# Accelerometer.net
KiCad netlist of a schematic drawn in Altium Designer
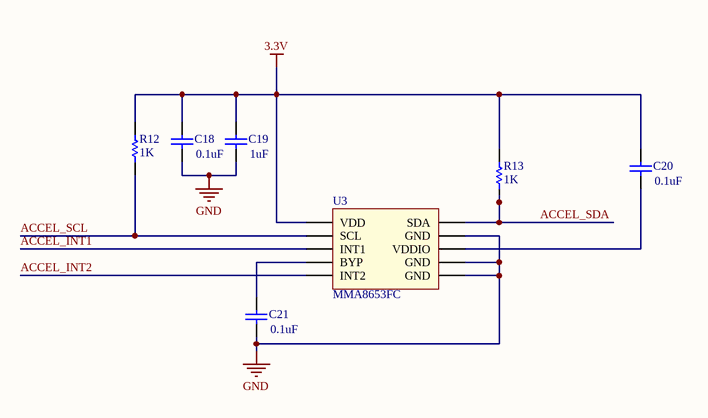
[diagram p0: Accelerometer.SchDoc]

(export (version "E")
  (design (tool "Eeschema 10.0.6"))
  (components
    (comp (ref "C18")
      (value "0.1uF")
      (footprint "0805")
      (description "Capacitor")
      (fields (field (name "Comment") "Cap"))
      (libsource (lib "passives") (part "Cap"))
    )
    (comp (ref "C19")
      (value "1uF")
      (footprint "0805")
      (description "Capacitor")
      (fields (field (name "Comment") "Cap"))
      (libsource (lib "passives") (part "Cap"))
    )
    (comp (ref "C20")
      (value "0.1uF")
      (footprint "0805")
      (description "Capacitor")
      (fields (field (name "Comment") "Cap"))
      (libsource (lib "passives") (part "Cap"))
    )
    (comp (ref "C21")
      (value "0.1uF")
      (footprint "0805")
      (description "Capacitor")
      (fields (field (name "Comment") "Cap"))
      (libsource (lib "passives") (part "Cap"))
    )
    (comp (ref "R12")
      (value "1K")
      (footprint "0805")
      (description "Resistor")
      (fields (field (name "PUBLISHER") "Altium Limited"))
      (libsource (lib "passives") (part "Resistor"))
    )
    (comp (ref "R13")
      (value "1K")
      (footprint "0805")
      (description "Resistor")
      (fields (field (name "PUBLISHER") "Altium Limited"))
      (libsource (lib "passives") (part "Resistor"))
    )
    (comp (ref "U3")
      (value "MMA8653FC")
      (footprint "DFN-10")
      (description "MMA8653FC Accelerometer 3-Axis")
      (libsource (lib "Devices") (part "MMA8653FC"))
    )
  )
  (nets
    (net (code "1") (name "/ACCEL_INT1") (class "Default")
      (node (ref "U3") (pin "3") (pinfunction "INT1_3") (pintype "passive"))
    )
    (net (code "2") (name "/ACCEL_INT2") (class "Default")
      (node (ref "U3") (pin "5") (pinfunction "INT2_5") (pintype "passive"))
    )
    (net (code "3") (name "/ACCEL_SCL") (class "Default")
      (node (ref "R12") (pin "1") (pinfunction "1_1") (pintype "passive"))
      (node (ref "U3") (pin "2") (pinfunction "SCL_2") (pintype "passive"))
    )
    (net (code "4") (name "/ACCEL_SDA") (class "Default")
      (node (ref "R13") (pin "1") (pinfunction "1_1") (pintype "passive"))
      (node (ref "U3") (pin "10") (pinfunction "SDA_10") (pintype "passive"))
    )
    (net (code "5") (name "3.3V") (class "Default")
      (node (ref "C18") (pin "2") (pinfunction "2_2") (pintype "passive"))
      (node (ref "C19") (pin "2") (pinfunction "2_2") (pintype "passive"))
      (node (ref "C20") (pin "2") (pinfunction "2_2") (pintype "passive"))
      (node (ref "R12") (pin "2") (pinfunction "2_2") (pintype "passive"))
      (node (ref "R13") (pin "2") (pinfunction "2_2") (pintype "passive"))
      (node (ref "U3") (pin "1") (pinfunction "VDD_1") (pintype "passive"))
    )
    (net (code "6") (name "GND") (class "Default")
      (node (ref "C18") (pin "1") (pinfunction "1_1") (pintype "passive"))
      (node (ref "C19") (pin "1") (pinfunction "1_1") (pintype "passive"))
      (node (ref "C21") (pin "1") (pinfunction "1_1") (pintype "passive"))
      (node (ref "U3") (pin "6") (pinfunction "GND_6") (pintype "passive"))
      (node (ref "U3") (pin "7") (pinfunction "GND_7") (pintype "passive"))
      (node (ref "U3") (pin "9") (pinfunction "GND_9") (pintype "passive"))
    )
    (net (code "7") (name "Net-(U3-BYP)") (class "Default")
      (node (ref "C21") (pin "2") (pinfunction "2_2") (pintype "passive"))
      (node (ref "U3") (pin "4") (pinfunction "BYP_4") (pintype "passive"))
    )
    (net (code "8") (name "Net-(U3-VDDIO)") (class "Default")
      (node (ref "C20") (pin "1") (pinfunction "1_1") (pintype "passive"))
      (node (ref "U3") (pin "8") (pinfunction "VDDIO_8") (pintype "passive"))
    )
  )
)
